# tumkibot1_servo_driver.net
KiCad netlist of a schematic drawn in EasyEDA Pro
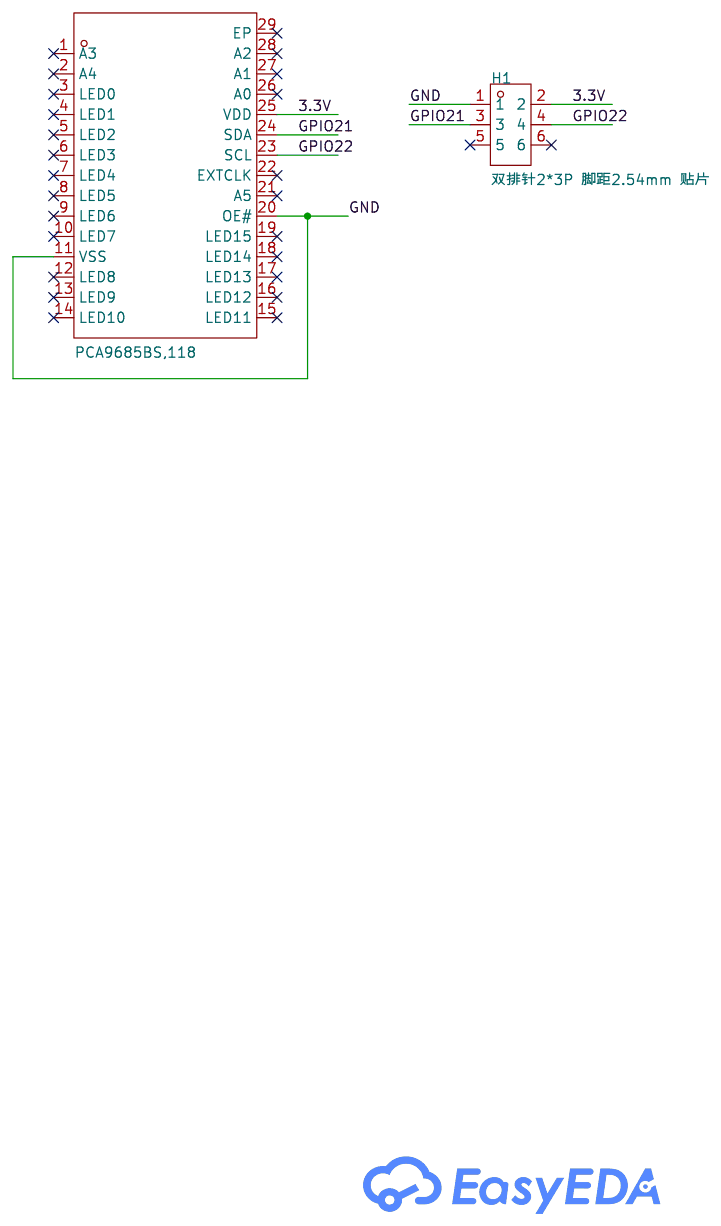
[diagram p0: schematic sheet]

(export (version "E")
  (design (tool "Eeschema 10.0.6"))
  (components
    (comp (ref "H1")
      (value "双排针2*3P 脚距2.54mm 贴片")
      (footprint "easyedapro:HDR-SMD_6P-P2.54-V-M-R2-C3-S2.54-LS7.4")
      (fields (field (name "Manufacturer") "BOOMELE(博穆精密)"))
      (libsource (lib "easyedapro") (part "双排针2*3P  脚距2.54MM  贴片"))
    )
    (comp (ref "U1")
      (value "PCA9685BS,118")
      (footprint "easyedapro:QFN-28_L6.0-W6.0-P0.65-TL-EP4.1")
      (fields (field (name "Manufacturer") "NXP(恩智浦)"))
      (libsource (lib "easyedapro") (part "PCA9685BS,118"))
    )
  )
  (nets
    (net (code "1") (name "/3.3V") (class "Default")
      (node (ref "H1") (pin "2") (pinfunction "2_2") (pintype "input"))
      (node (ref "U1") (pin "25") (pinfunction "VDD_25") (pintype "unspecified"))
    )
    (net (code "2") (name "/GND") (class "Default")
      (node (ref "H1") (pin "1") (pinfunction "1_1") (pintype "input"))
      (node (ref "U1") (pin "11") (pinfunction "VSS_11") (pintype "unspecified"))
      (node (ref "U1") (pin "20") (pinfunction "OE#_20") (pintype "unspecified"))
    )
    (net (code "3") (name "/GPIO21") (class "Default")
      (node (ref "H1") (pin "3") (pinfunction "3_3") (pintype "input"))
      (node (ref "U1") (pin "24") (pinfunction "SDA_24") (pintype "unspecified"))
    )
    (net (code "4") (name "/GPIO22") (class "Default")
      (node (ref "H1") (pin "4") (pinfunction "4_4") (pintype "input"))
      (node (ref "U1") (pin "23") (pinfunction "SCL_23") (pintype "unspecified"))
    )
    (net (code "5") (name "unconnected-(H1-Pad5)") (class "Default")
      (node (ref "H1") (pin "5") (pinfunction "5_5") (pintype "input+no_connect"))
    )
    (net (code "6") (name "unconnected-(H1-Pad6)") (class "Default")
      (node (ref "H1") (pin "6") (pinfunction "6_6") (pintype "input+no_connect"))
    )
    (net (code "7") (name "unconnected-(U1-A0-Pad26)") (class "Default")
      (node (ref "U1") (pin "26") (pinfunction "A0_26") (pintype "unspecified+no_connect"))
    )
    (net (code "8") (name "unconnected-(U1-A1-Pad27)") (class "Default")
      (node (ref "U1") (pin "27") (pinfunction "A1_27") (pintype "unspecified+no_connect"))
    )
    (net (code "9") (name "unconnected-(U1-A2-Pad28)") (class "Default")
      (node (ref "U1") (pin "28") (pinfunction "A2_28") (pintype "unspecified+no_connect"))
    )
    (net (code "10") (name "unconnected-(U1-A3-Pad1)") (class "Default")
      (node (ref "U1") (pin "1") (pinfunction "A3_1") (pintype "unspecified+no_connect"))
    )
    (net (code "11") (name "unconnected-(U1-A4-Pad2)") (class "Default")
      (node (ref "U1") (pin "2") (pinfunction "A4_2") (pintype "unspecified+no_connect"))
    )
    (net (code "12") (name "unconnected-(U1-A5-Pad21)") (class "Default")
      (node (ref "U1") (pin "21") (pinfunction "A5_21") (pintype "unspecified+no_connect"))
    )
    (net (code "13") (name "unconnected-(U1-EP-Pad29)") (class "Default")
      (node (ref "U1") (pin "29") (pinfunction "EP_29") (pintype "unspecified+no_connect"))
    )
    (net (code "14") (name "unconnected-(U1-EXTCLK-Pad22)") (class "Default")
      (node (ref "U1") (pin "22") (pinfunction "EXTCLK_22") (pintype "unspecified+no_connect"))
    )
    (net (code "15") (name "unconnected-(U1-LED0-Pad3)") (class "Default")
      (node (ref "U1") (pin "3") (pinfunction "LED0_3") (pintype "unspecified+no_connect"))
    )
    (net (code "16") (name "unconnected-(U1-LED1-Pad4)") (class "Default")
      (node (ref "U1") (pin "4") (pinfunction "LED1_4") (pintype "unspecified+no_connect"))
    )
    (net (code "17") (name "unconnected-(U1-LED2-Pad5)") (class "Default")
      (node (ref "U1") (pin "5") (pinfunction "LED2_5") (pintype "unspecified+no_connect"))
    )
    (net (code "18") (name "unconnected-(U1-LED3-Pad6)") (class "Default")
      (node (ref "U1") (pin "6") (pinfunction "LED3_6") (pintype "unspecified+no_connect"))
    )
    (net (code "19") (name "unconnected-(U1-LED4-Pad7)") (class "Default")
      (node (ref "U1") (pin "7") (pinfunction "LED4_7") (pintype "unspecified+no_connect"))
    )
    (net (code "20") (name "unconnected-(U1-LED5-Pad8)") (class "Default")
      (node (ref "U1") (pin "8") (pinfunction "LED5_8") (pintype "unspecified+no_connect"))
    )
    (net (code "21") (name "unconnected-(U1-LED6-Pad9)") (class "Default")
      (node (ref "U1") (pin "9") (pinfunction "LED6_9") (pintype "unspecified+no_connect"))
    )
    (net (code "22") (name "unconnected-(U1-LED7-Pad10)") (class "Default")
      (node (ref "U1") (pin "10") (pinfunction "LED7_10") (pintype "unspecified+no_connect"))
    )
    (net (code "23") (name "unconnected-(U1-LED8-Pad12)") (class "Default")
      (node (ref "U1") (pin "12") (pinfunction "LED8_12") (pintype "unspecified+no_connect"))
    )
    (net (code "24") (name "unconnected-(U1-LED9-Pad13)") (class "Default")
      (node (ref "U1") (pin "13") (pinfunction "LED9_13") (pintype "unspecified+no_connect"))
    )
    (net (code "25") (name "unconnected-(U1-LED10-Pad14)") (class "Default")
      (node (ref "U1") (pin "14") (pinfunction "LED10_14") (pintype "unspecified+no_connect"))
    )
    (net (code "26") (name "unconnected-(U1-LED11-Pad15)") (class "Default")
      (node (ref "U1") (pin "15") (pinfunction "LED11_15") (pintype "unspecified+no_connect"))
    )
    (net (code "27") (name "unconnected-(U1-LED12-Pad16)") (class "Default")
      (node (ref "U1") (pin "16") (pinfunction "LED12_16") (pintype "unspecified+no_connect"))
    )
    (net (code "28") (name "unconnected-(U1-LED13-Pad17)") (class "Default")
      (node (ref "U1") (pin "17") (pinfunction "LED13_17") (pintype "unspecified+no_connect"))
    )
    (net (code "29") (name "unconnected-(U1-LED14-Pad18)") (class "Default")
      (node (ref "U1") (pin "18") (pinfunction "LED14_18") (pintype "unspecified+no_connect"))
    )
    (net (code "30") (name "unconnected-(U1-LED15-Pad19)") (class "Default")
      (node (ref "U1") (pin "19") (pinfunction "LED15_19") (pintype "unspecified+no_connect"))
    )
  )
)
